# DownstreamPort.net
KiCad netlist of a schematic drawn in Altium Designer
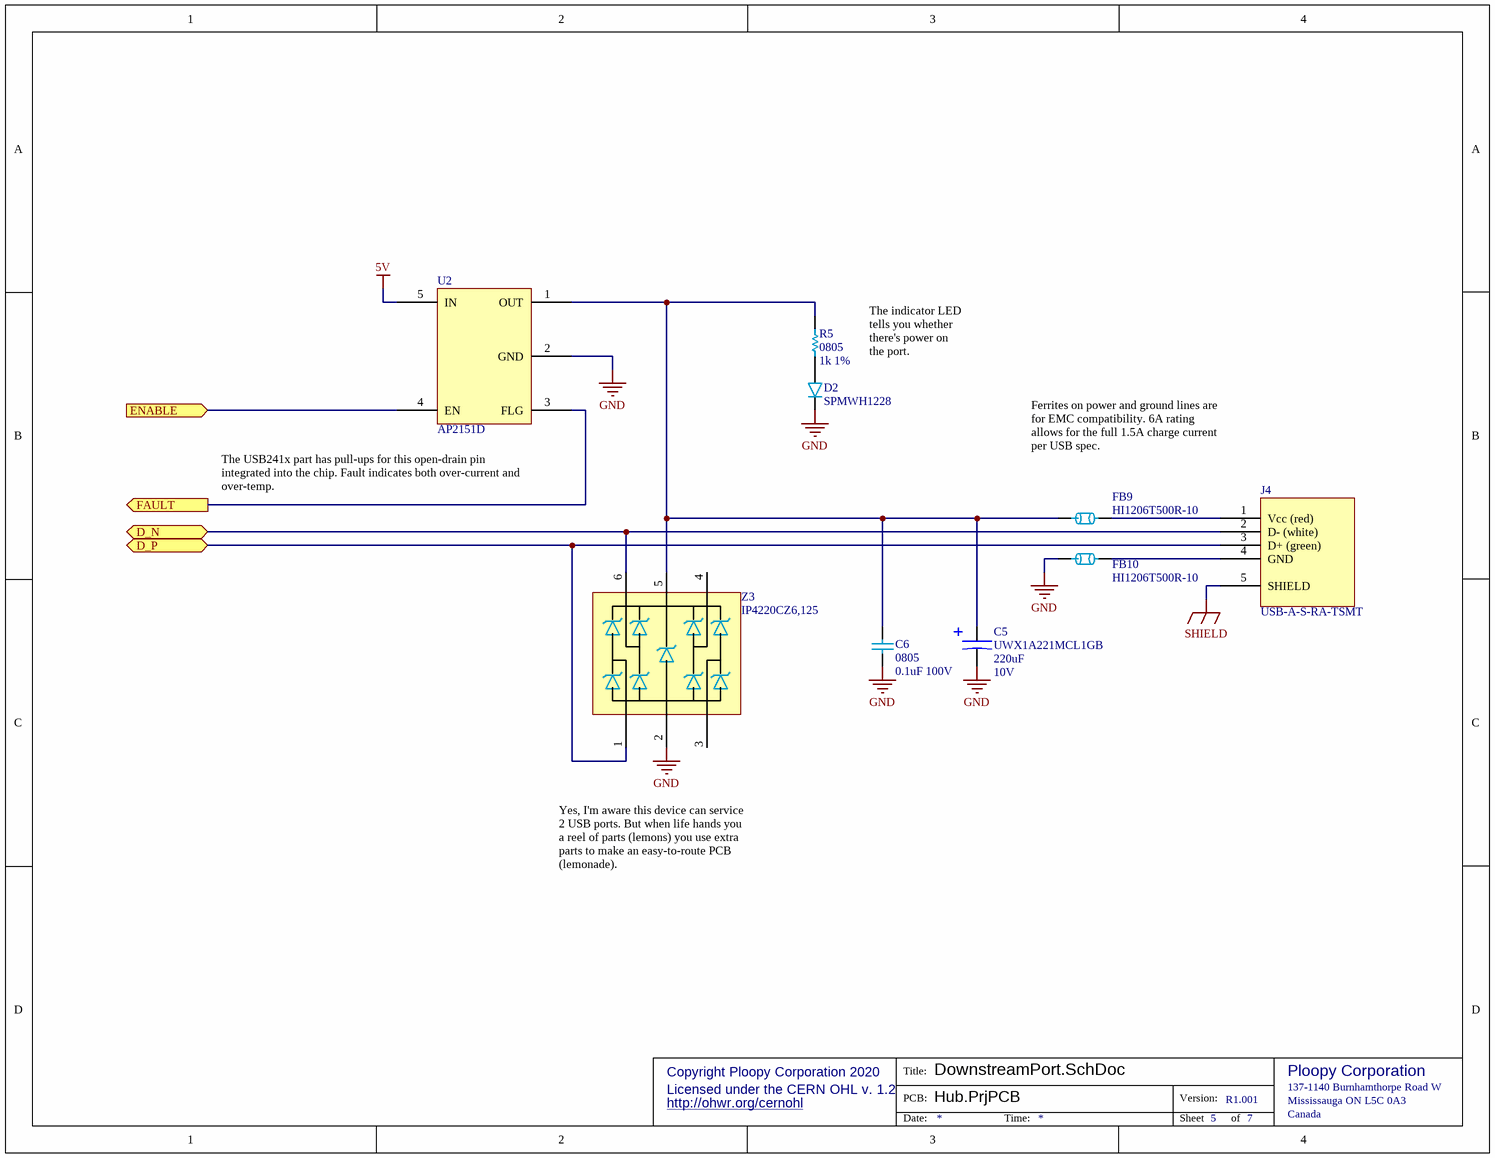
[diagram p0: DownstreamPort.SchDoc]

(export (version "E")
  (design (tool "Eeschema 10.0.6"))
  (components
    (comp (ref "C5")
      (value "UWX1A221MCL1GB")
      (footprint "Nichicon UWX - 8mm x 5.5mm")
      (description "220uF 10V Electrolytic Capacitor, SMD")
      (fields (field (name "ALTIUM_VALUE") "220uF") (field (name "VOLTAGE") "10V"))
      (libsource (lib "Capacitors") (part "UWX1A221MCL1GB"))
    )
    (comp (ref "C6")
      (value "0805")
      (footprint "0805")
      (description "0805, X5R or better")
      (fields (field (name "ALTIUM_VALUE") "0.1uF 100V"))
      (libsource (lib "Chip_Passives") (part "Cap 0.1uF 100V"))
    )
    (comp (ref "D2")
      (value "SPMWH1228")
      (footprint "SPMWH1228")
      (description "3V/0.5W white LED, 2.8mm x 3.5mm")
      (libsource (lib "LEDs") (part "SPMWH1228"))
    )
    (comp (ref "FB9")
      (value "HI1206T500R-10")
      (footprint "1206")
      (description "50 Ohms @ 100MHz 1 Power, Signal Line Ferrite Bead 1206 (3216 Metric) 6A 10mOhm")
      (libsource (lib "Chip_Passives") (part "HI1206T500R-10"))
    )
    (comp (ref "FB10")
      (value "HI1206T500R-10")
      (footprint "1206")
      (description "50 Ohms @ 100MHz 1 Power, Signal Line Ferrite Bead 1206 (3216 Metric) 6A 10mOhm")
      (libsource (lib "Chip_Passives") (part "HI1206T500R-10"))
    )
    (comp (ref "J4")
      (value "USB-A-S-RA-TSMT")
      (footprint "USB-A-S-RA-TSMT")
      (description "USB - A USB 2.0 Receptacle Connector 4 Position Surface Mount, Right Angle")
      (libsource (lib "Connectors") (part "USB-A-S-RA-TSMT"))
    )
    (comp (ref "R5")
      (value "0805")
      (footprint "0805")
      (description "Chip resistor, 1/8W 100PPM")
      (fields (field (name "ALTIUM_VALUE") "1k 1%"))
      (libsource (lib "Chip_Passives") (part "Res 1k 1% 0805"))
    )
    (comp (ref "U2")
      (value "AP2151D")
      (footprint "AP22811 - SOT95P285X140-5M")
      (description "USB Power Switch/Driver 500mA SOT-25")
      (libsource (lib "PowerSupply") (part "AP2151D"))
    )
    (comp (ref "Z3")
      (value "IP4220CZ6,125")
      (footprint "PESD3V3S4UD - SOT95P275X110-6N")
      (description "TVS DIODE 5.5V 6TSOP (Low capacitance, USB)")
      (libsource (lib "Diodes") (part "IP4220CZ6,125"))
    )
  )
  (nets
    (net (code "1") (name "/D_N") (class "Default")
      (node (ref "J4") (pin "2") (pinfunction "D-_(white)_2") (pintype "passive"))
      (node (ref "Z3") (pin "6") (pinfunction "6_6") (pintype "passive"))
    )
    (net (code "2") (name "/D_P") (class "Default")
      (node (ref "J4") (pin "3") (pinfunction "D+_(green)_3") (pintype "passive"))
      (node (ref "Z3") (pin "1") (pinfunction "1_1") (pintype "passive"))
    )
    (net (code "3") (name "/ENABLE") (class "Default")
      (node (ref "U2") (pin "4") (pinfunction "EN_4") (pintype "passive"))
    )
    (net (code "4") (name "/FAULT") (class "Default")
      (node (ref "U2") (pin "3") (pinfunction "FLG_3") (pintype "passive"))
    )
    (net (code "5") (name "5V") (class "Default")
      (node (ref "U2") (pin "5") (pinfunction "IN_5") (pintype "passive"))
    )
    (net (code "6") (name "GND") (class "Default")
      (node (ref "C5") (pin "2") (pinfunction "2_2") (pintype "passive"))
      (node (ref "C6") (pin "1") (pinfunction "1_1") (pintype "passive"))
      (node (ref "D2") (pin "2") (pinfunction "C_2") (pintype "passive"))
      (node (ref "FB10") (pin "1") (pinfunction "1_1") (pintype "passive"))
      (node (ref "U2") (pin "2") (pinfunction "GND_2") (pintype "passive"))
      (node (ref "Z3") (pin "2") (pinfunction "2_2") (pintype "passive"))
    )
    (net (code "7") (name "Net-(D2-A)") (class "Default")
      (node (ref "D2") (pin "1") (pinfunction "A_1") (pintype "passive"))
      (node (ref "R5") (pin "1") (pinfunction "1_1") (pintype "passive"))
    )
    (net (code "8") (name "Net-(J4-GND)") (class "Default")
      (node (ref "FB10") (pin "2") (pinfunction "2_2") (pintype "passive"))
      (node (ref "J4") (pin "4") (pinfunction "GND_4") (pintype "passive"))
    )
    (net (code "9") (name "Net-(J4-Vcc_(red))") (class "Default")
      (node (ref "FB9") (pin "2") (pinfunction "2_2") (pintype "passive"))
      (node (ref "J4") (pin "1") (pinfunction "Vcc_(red)_1") (pintype "passive"))
    )
    (net (code "10") (name "Net-(U2-OUT)") (class "Default")
      (node (ref "C5") (pin "1") (pinfunction "1_1") (pintype "passive"))
      (node (ref "C6") (pin "2") (pinfunction "2_2") (pintype "passive"))
      (node (ref "FB9") (pin "1") (pinfunction "1_1") (pintype "passive"))
      (node (ref "R5") (pin "2") (pinfunction "2_2") (pintype "passive"))
      (node (ref "U2") (pin "1") (pinfunction "OUT_1") (pintype "passive"))
      (node (ref "Z3") (pin "5") (pinfunction "5_5") (pintype "passive"))
    )
    (net (code "11") (name "SHIELD") (class "Default")
      (node (ref "J4") (pin "5") (pinfunction "SHIELD_5") (pintype "passive"))
    )
    (net (code "12") (name "unconnected-(Z3-Pad3)") (class "Default")
      (node (ref "Z3") (pin "3") (pinfunction "3_3") (pintype "passive"))
    )
    (net (code "13") (name "unconnected-(Z3-Pad4)") (class "Default")
      (node (ref "Z3") (pin "4") (pinfunction "4_4") (pintype "passive"))
    )
  )
)
